# SWD.net
KiCad netlist of a schematic drawn in Altium Designer
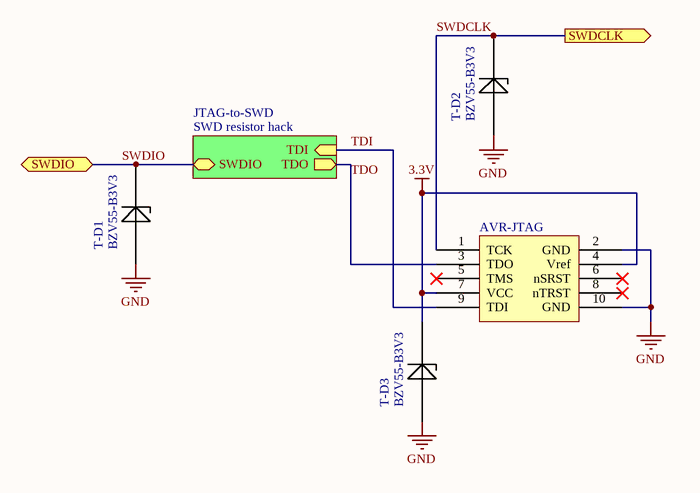
[diagram p0: SWD.SchDoc]

(export (version "E")
  (design (tool "Eeschema 10.0.6"))
  (components
    (comp (ref "AVR-JTAG")
      (value "AVR Style")
      (footprint "Header 2x5 IDC-10S")
      (libsource (lib "Headers") (part "Header JTAG AVR"))
    )
    (comp (ref "T-D1")
      (value "BZV55-B3V3")
      (footprint "Minimelf")
      (libsource (lib "Standard") (part "Zener Diode"))
    )
    (comp (ref "T-D2")
      (value "BZV55-B3V3")
      (footprint "Minimelf")
      (libsource (lib "Standard") (part "Zener Diode"))
    )
    (comp (ref "T-D3")
      (value "BZV55-B3V3")
      (footprint "Minimelf")
      (libsource (lib "Standard") (part "Zener Diode"))
    )
  )
  (nets
    (net (code "1") (name "/SWDCLK") (class "Default")
      (node (ref "AVR-JTAG") (pin "1") (pinfunction "TCK_1") (pintype "passive"))
      (node (ref "T-D2") (pin "1") (pinfunction "1_1") (pintype "passive"))
    )
    (net (code "2") (name "/SWDIO") (class "Default")
      (node (ref "T-D1") (pin "1") (pinfunction "1_1") (pintype "passive"))
    )
    (net (code "3") (name "/TDI") (class "Default")
      (node (ref "AVR-JTAG") (pin "9") (pinfunction "TDI_9") (pintype "passive"))
    )
    (net (code "4") (name "/TDO") (class "Default")
      (node (ref "AVR-JTAG") (pin "3") (pinfunction "TDO_3") (pintype "passive"))
    )
    (net (code "5") (name "3.3V") (class "Default")
      (node (ref "AVR-JTAG") (pin "4") (pinfunction "Vref_4") (pintype "passive"))
      (node (ref "AVR-JTAG") (pin "7") (pinfunction "VCC_7") (pintype "passive"))
      (node (ref "T-D3") (pin "1") (pinfunction "1_1") (pintype "passive"))
    )
    (net (code "6") (name "GND") (class "Default")
      (node (ref "AVR-JTAG") (pin "10") (pinfunction "GND_10") (pintype "passive"))
      (node (ref "AVR-JTAG") (pin "2") (pinfunction "GND_2") (pintype "passive"))
      (node (ref "T-D1") (pin "2") (pinfunction "2_2") (pintype "passive"))
      (node (ref "T-D2") (pin "2") (pinfunction "2_2") (pintype "passive"))
      (node (ref "T-D3") (pin "2") (pinfunction "2_2") (pintype "passive"))
    )
    (net (code "7") (name "unconnected-(AVR-JTAG-TMS-Pad5)") (class "Default")
      (node (ref "AVR-JTAG") (pin "5") (pinfunction "TMS_5") (pintype "passive+no_connect"))
    )
    (net (code "8") (name "unconnected-(AVR-JTAG-nSRST-Pad6)") (class "Default")
      (node (ref "AVR-JTAG") (pin "6") (pinfunction "nSRST_6") (pintype "passive+no_connect"))
    )
    (net (code "9") (name "unconnected-(AVR-JTAG-nTRST-Pad8)") (class "Default")
      (node (ref "AVR-JTAG") (pin "8") (pinfunction "nTRST_8") (pintype "passive+no_connect"))
    )
  )
)
